# IMU.net
KiCad netlist of a schematic drawn in Altium Designer
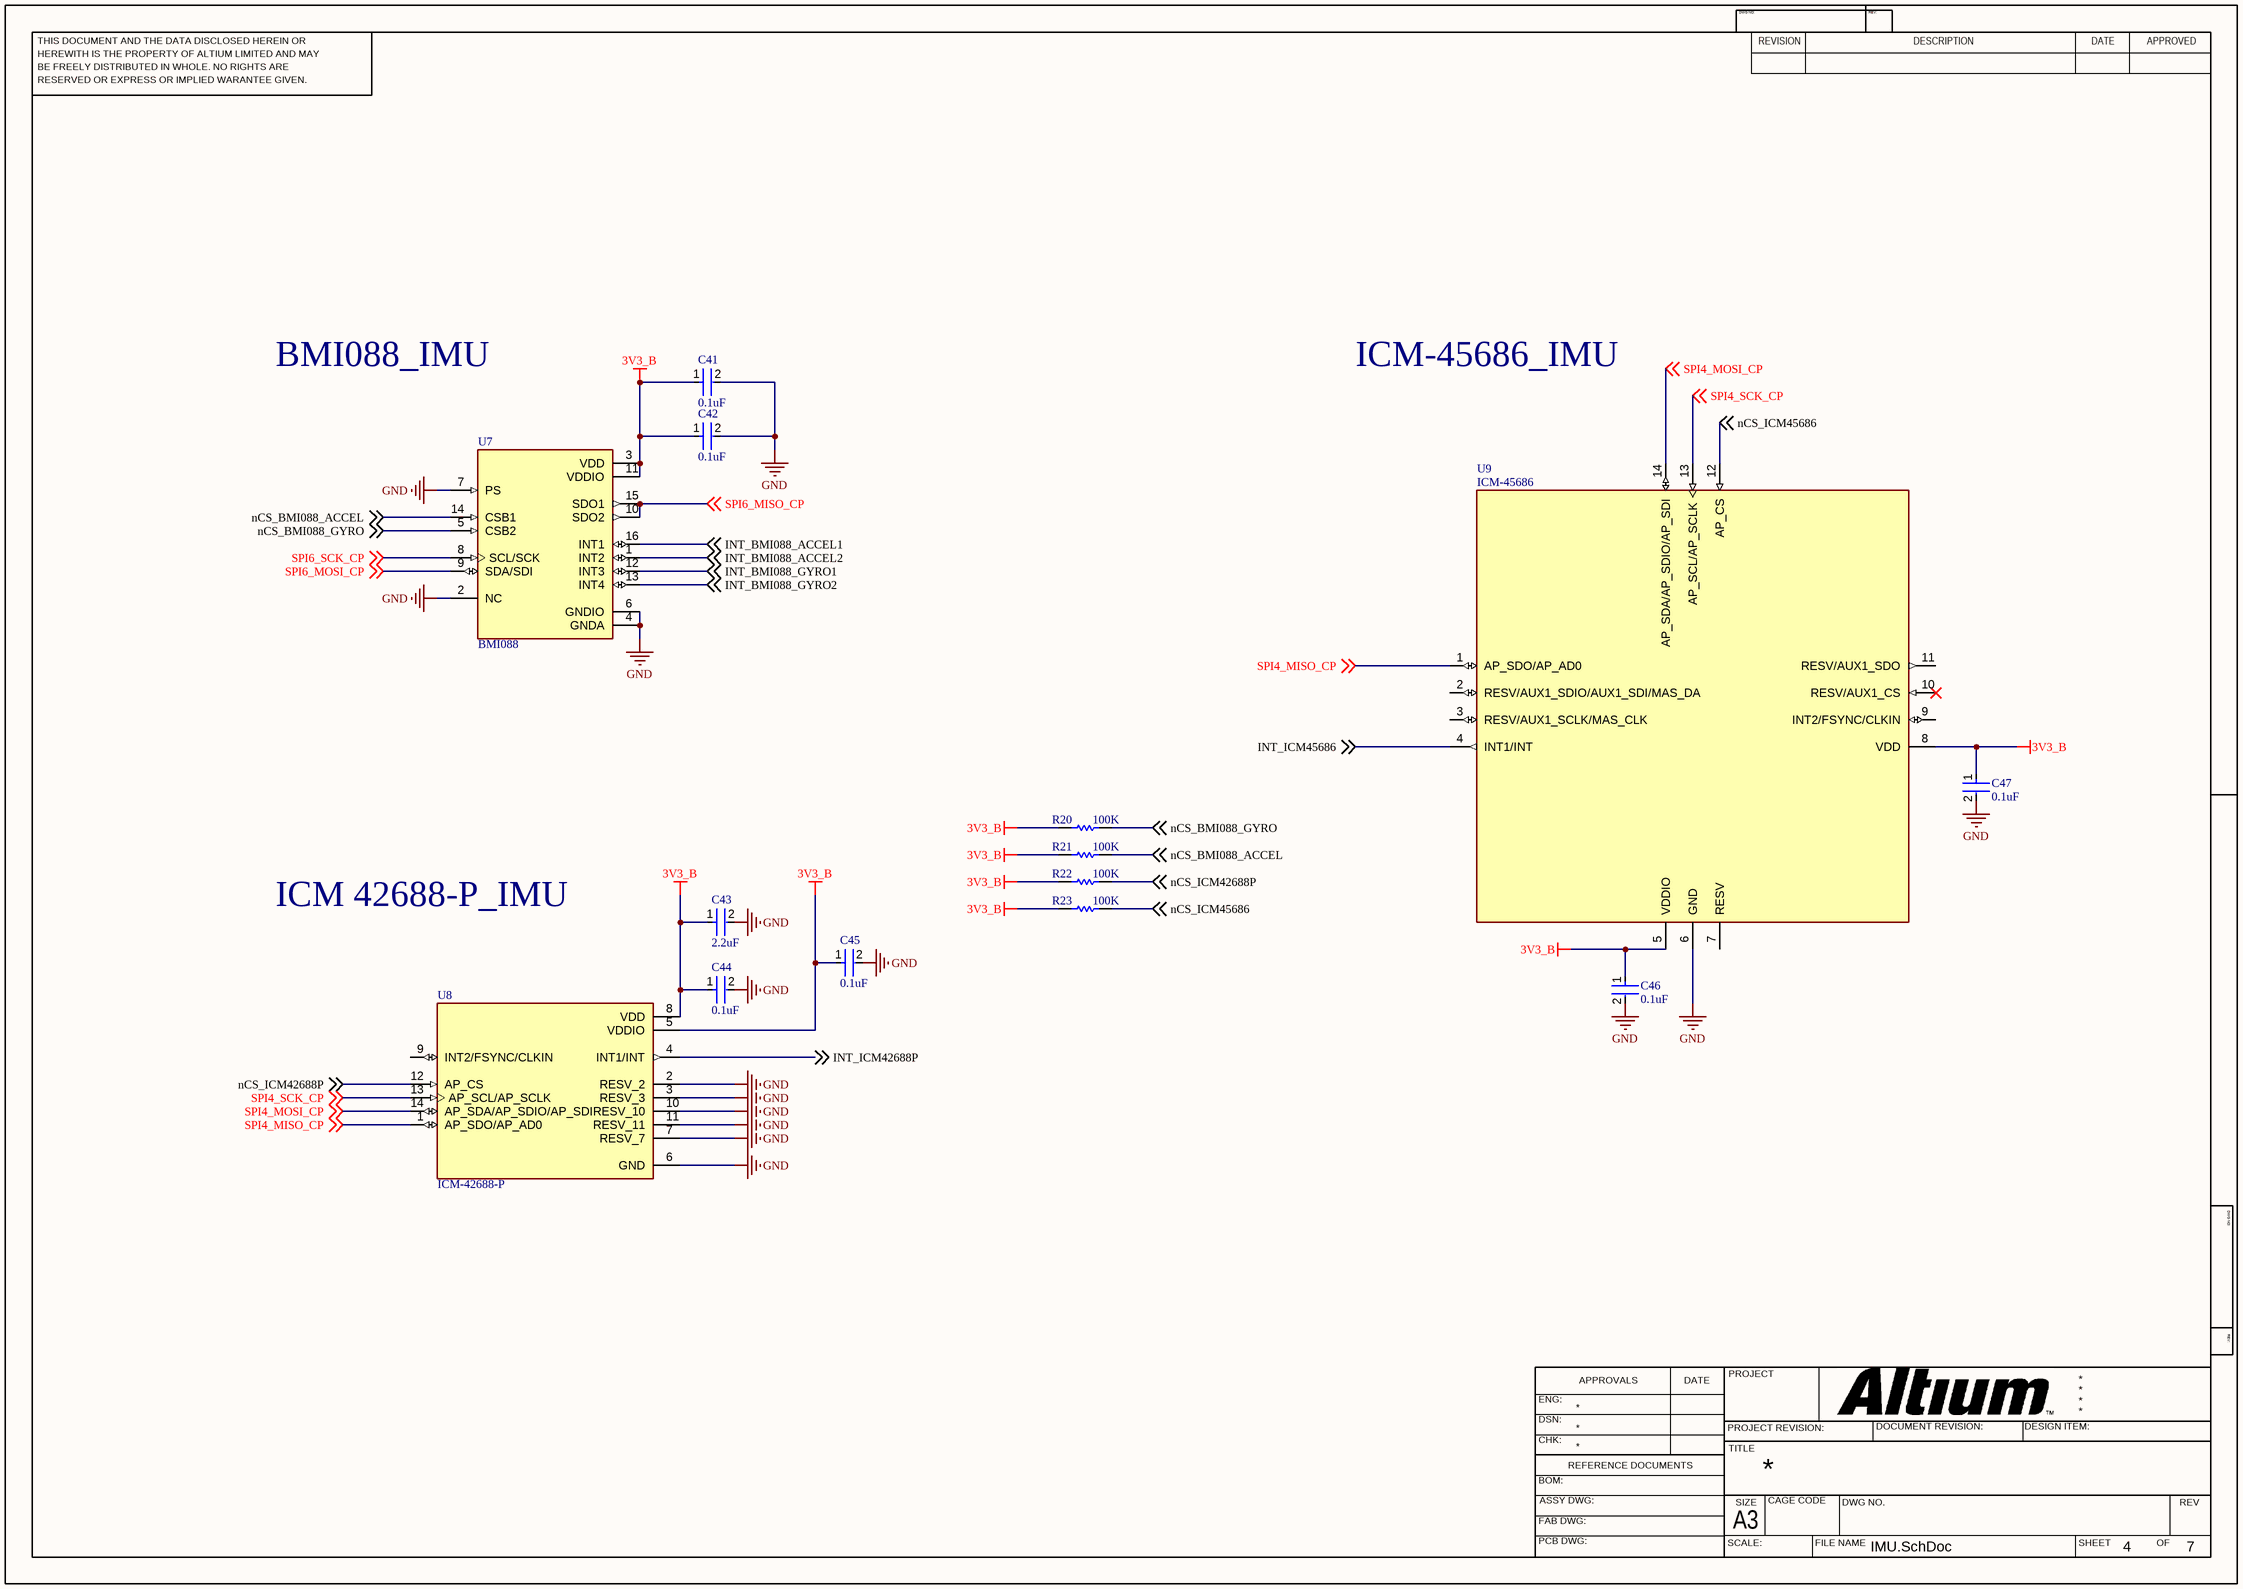
[diagram p0: IMU.SchDoc]

(export (version "E")
  (design (tool "Eeschema 10.0.6"))
  (components
    (comp (ref "C41")
      (value "0.1uF")
      (footprint "FP-C0603C-CF-MFG")
      (description "CAP CER 0.1UF 50V X7R 0603")
      (fields (field (name "TOLERANCE") "0.1") (field (name "MANUFACTURER") "KEMET"))
      (libsource (lib "Altium Content Vault") (part "b4654b650e69147ec39a6b967a45e02"))
    )
    (comp (ref "C42")
      (value "0.1uF")
      (footprint "FP-C0603C-CF-MFG")
      (description "CAP CER 0.1UF 50V X7R 0603")
      (fields (field (name "TOLERANCE") "0.1") (field (name "MANUFACTURER") "KEMET"))
      (libsource (lib "Altium Content Vault") (part "b4654b650e69147ec39a6b967a45e02"))
    )
    (comp (ref "C43")
      (value "2.2uF")
      (footprint "FP-GRM188-0_1-e0_2_0_5-MFG")
      (description "Chip Multilayer Ceramic Capacitors for General Purpose, 0603, 2.2uF, X7R, 15%, 10%, 10V")
      (fields (field (name "VOLTAGE") "10V") (field (name "TOLERANCE") "10%"))
      (libsource (lib "Altium Content Vault") (part "11868f565c42a9108669ba33697ecf6"))
    )
    (comp (ref "C44")
      (value "0.1uF")
      (footprint "FP-C0603C-CF-MFG")
      (description "CAP CER 0.1UF 50V X7R 0603")
      (fields (field (name "TOLERANCE") "0.1") (field (name "MANUFACTURER") "KEMET"))
      (libsource (lib "Altium Content Vault") (part "b4654b650e69147ec39a6b967a45e02"))
    )
    (comp (ref "C45")
      (value "0.1uF")
      (footprint "FP-C0603C-CF-MFG")
      (description "CAP CER 0.1UF 50V X7R 0603")
      (fields (field (name "TOLERANCE") "0.1") (field (name "MANUFACTURER") "KEMET"))
      (libsource (lib "Altium Content Vault") (part "b4654b650e69147ec39a6b967a45e02"))
    )
    (comp (ref "C46")
      (value "0.1uF")
      (footprint "FP-C0603C-CF-MFG")
      (description "CAP CER 0.1UF 50V X7R 0603")
      (fields (field (name "TOLERANCE") "0.1") (field (name "MANUFACTURER") "KEMET"))
      (libsource (lib "Altium Content Vault") (part "b4654b650e69147ec39a6b967a45e02"))
    )
    (comp (ref "C47")
      (value "0.1uF")
      (footprint "FP-C0603C-CF-MFG")
      (description "CAP CER 0.1UF 50V X7R 0603")
      (fields (field (name "TOLERANCE") "0.1") (field (name "MANUFACTURER") "KEMET"))
      (libsource (lib "Altium Content Vault") (part "b4654b650e69147ec39a6b967a45e02"))
    )
    (comp (ref "R20")
      (value "100K")
      (footprint "RESC1608X55X30ML20T10")
      (fields (field (name "PART NUMBER") "RK73B1JTTD104J") (field (name "MANUFACTURER") "KOA Speer"))
      (libsource (lib "Altium Content Vault") (part "RES"))
    )
    (comp (ref "R21")
      (value "100K")
      (footprint "RESC1608X55X30ML20T10")
      (fields (field (name "PART NUMBER") "RK73B1JTTD104J") (field (name "MANUFACTURER") "KOA Speer"))
      (libsource (lib "Altium Content Vault") (part "RES"))
    )
    (comp (ref "R22")
      (value "100K")
      (footprint "RESC1608X55X30ML20T10")
      (fields (field (name "PART NUMBER") "RK73B1JTTD104J") (field (name "MANUFACTURER") "KOA Speer"))
      (libsource (lib "Altium Content Vault") (part "RES"))
    )
    (comp (ref "R23")
      (value "100K")
      (footprint "RESC1608X55X30ML20T10")
      (fields (field (name "PART NUMBER") "RK73B1JTTD104J") (field (name "MANUFACTURER") "KOA Speer"))
      (libsource (lib "Altium Content Vault") (part "RES"))
    )
    (comp (ref "U7")
      (value "BMI088")
      (footprint "PQFN50P450X300X100-16N")
      (libsource (lib "Hitesh Bhoyar") (part "BMI088"))
    )
    (comp (ref "U8")
      (value "ICM-42688-P")
      (footprint "PQFN50P300X250X97-14N")
      (description "Accelerometer, Gyroscope, 6 Axis Sensor Output")
      (libsource (lib "Hitesh Bhoyar") (part "ICM-42688-P"))
    )
    (comp (ref "U9")
      (value "ICM-45686")
      (footprint "IC_ICM-45686")
      (description "Accelerometer, Gyroscope, 6 Axis Sensor I2C, I3C, SPI Output")
      (fields (field (name "MF") "TDK InvenSense"))
      (libsource (lib "Hitesh Bhoyar") (part "ICM-45686"))
    )
  )
  (nets
    (net (code "1") (name "3V3_B") (class "Default")
      (node (ref "C41") (pin "1") (pinfunction "1_1") (pintype "passive"))
      (node (ref "C42") (pin "1") (pinfunction "1_1") (pintype "passive"))
      (node (ref "C43") (pin "1") (pinfunction "1_1") (pintype "passive"))
      (node (ref "C44") (pin "1") (pinfunction "1_1") (pintype "passive"))
      (node (ref "C45") (pin "1") (pinfunction "1_1") (pintype "passive"))
      (node (ref "C46") (pin "1") (pinfunction "1_1") (pintype "passive"))
      (node (ref "C47") (pin "1") (pinfunction "1_1") (pintype "passive"))
      (node (ref "R20") (pin "2") (pinfunction "2_2") (pintype "passive"))
      (node (ref "R21") (pin "2") (pinfunction "2_2") (pintype "passive"))
      (node (ref "R22") (pin "2") (pinfunction "2_2") (pintype "passive"))
      (node (ref "R23") (pin "2") (pinfunction "2_2") (pintype "passive"))
      (node (ref "U7") (pin "11") (pinfunction "VDDIO_11") (pintype "power_in"))
      (node (ref "U7") (pin "3") (pinfunction "VDD_3") (pintype "power_in"))
      (node (ref "U8") (pin "5") (pinfunction "VDDIO_5") (pintype "power_in"))
      (node (ref "U8") (pin "8") (pinfunction "VDD_8") (pintype "power_in"))
      (node (ref "U9") (pin "5") (pinfunction "VDDIO_5") (pintype "power_in"))
      (node (ref "U9") (pin "8") (pinfunction "VDD_8") (pintype "power_in"))
    )
    (net (code "2") (name "GND") (class "Default")
      (node (ref "C41") (pin "2") (pinfunction "2_2") (pintype "passive"))
      (node (ref "C42") (pin "2") (pinfunction "2_2") (pintype "passive"))
      (node (ref "C43") (pin "2") (pinfunction "2_2") (pintype "passive"))
      (node (ref "C44") (pin "2") (pinfunction "2_2") (pintype "passive"))
      (node (ref "C45") (pin "2") (pinfunction "2_2") (pintype "passive"))
      (node (ref "C46") (pin "2") (pinfunction "2_2") (pintype "passive"))
      (node (ref "C47") (pin "2") (pinfunction "2_2") (pintype "passive"))
      (node (ref "U7") (pin "2") (pinfunction "NC_2") (pintype "passive"))
      (node (ref "U7") (pin "4") (pinfunction "GNDA_4") (pintype "power_in"))
      (node (ref "U7") (pin "6") (pinfunction "GNDIO_6") (pintype "power_in"))
      (node (ref "U7") (pin "7") (pinfunction "PS_7") (pintype "input"))
      (node (ref "U8") (pin "10") (pinfunction "RESV_10_10") (pintype "passive"))
      (node (ref "U8") (pin "11") (pinfunction "RESV_11_11") (pintype "passive"))
      (node (ref "U8") (pin "2") (pinfunction "RESV_2_2") (pintype "passive"))
      (node (ref "U8") (pin "3") (pinfunction "RESV_3_3") (pintype "passive"))
      (node (ref "U8") (pin "6") (pinfunction "GND_6") (pintype "power_in"))
      (node (ref "U8") (pin "7") (pinfunction "RESV_7_7") (pintype "passive"))
      (node (ref "U9") (pin "6") (pinfunction "GND_6") (pintype "power_in"))
    )
    (net (code "3") (name "INT_BMI088_ACCEL1") (class "Default")
      (node (ref "U7") (pin "16") (pinfunction "INT1_16") (pintype "bidirectional"))
    )
    (net (code "4") (name "INT_BMI088_ACCEL2") (class "Default")
      (node (ref "U7") (pin "1") (pinfunction "INT2_1") (pintype "bidirectional"))
    )
    (net (code "5") (name "INT_BMI088_GYRO1") (class "Default")
      (node (ref "U7") (pin "12") (pinfunction "INT3_12") (pintype "bidirectional"))
    )
    (net (code "6") (name "INT_BMI088_GYRO2") (class "Default")
      (node (ref "U7") (pin "13") (pinfunction "INT4_13") (pintype "bidirectional"))
    )
    (net (code "7") (name "INT_ICM42688P") (class "Default")
      (node (ref "U8") (pin "4") (pinfunction "INT1/INT_4") (pintype "output"))
    )
    (net (code "8") (name "INT_ICM45686") (class "Default")
      (node (ref "U9") (pin "4") (pinfunction "INT1/INT_4") (pintype "output"))
    )
    (net (code "9") (name "SPI4_MISO_CP") (class "Default")
      (node (ref "U8") (pin "1") (pinfunction "AP_SDO/AP_AD0_1") (pintype "bidirectional"))
      (node (ref "U9") (pin "1") (pinfunction "AP_SDO/AP_AD0_1") (pintype "bidirectional"))
    )
    (net (code "10") (name "SPI4_MOSI_CP") (class "Default")
      (node (ref "U8") (pin "14") (pinfunction "AP_SDA/AP_SDIO/AP_SDI_14") (pintype "bidirectional"))
      (node (ref "U9") (pin "14") (pinfunction "AP_SDA/AP_SDIO/AP_SDI_14") (pintype "bidirectional"))
    )
    (net (code "11") (name "SPI4_SCK_CP") (class "Default")
      (node (ref "U8") (pin "13") (pinfunction "AP_SCL/AP_SCLK_13") (pintype "input"))
      (node (ref "U9") (pin "13") (pinfunction "AP_SCL/AP_SCLK_13") (pintype "input"))
    )
    (net (code "12") (name "SPI6_MISO_CP") (class "Default")
      (node (ref "U7") (pin "10") (pinfunction "SDO2_10") (pintype "output"))
      (node (ref "U7") (pin "15") (pinfunction "SDO1_15") (pintype "output"))
    )
    (net (code "13") (name "SPI6_MOSI_CP") (class "Default")
      (node (ref "U7") (pin "9") (pinfunction "SDA/SDI_9") (pintype "bidirectional"))
    )
    (net (code "14") (name "SPI6_SCK_CP") (class "Default")
      (node (ref "U7") (pin "8") (pinfunction "SCL/SCK_8") (pintype "input"))
    )
    (net (code "15") (name "nCS_BMI088_ACCEL") (class "Default")
      (node (ref "R21") (pin "1") (pinfunction "1_1") (pintype "passive"))
      (node (ref "U7") (pin "14") (pinfunction "CSB1_14") (pintype "input"))
    )
    (net (code "16") (name "nCS_BMI088_GYRO") (class "Default")
      (node (ref "R20") (pin "1") (pinfunction "1_1") (pintype "passive"))
      (node (ref "U7") (pin "5") (pinfunction "CSB2_5") (pintype "input"))
    )
    (net (code "17") (name "nCS_ICM42688P") (class "Default")
      (node (ref "R22") (pin "1") (pinfunction "1_1") (pintype "passive"))
      (node (ref "U8") (pin "12") (pinfunction "AP_CS_12") (pintype "input"))
    )
    (net (code "18") (name "nCS_ICM45686") (class "Default")
      (node (ref "R23") (pin "1") (pinfunction "1_1") (pintype "passive"))
      (node (ref "U9") (pin "12") (pinfunction "AP_CS_12") (pintype "input"))
    )
    (net (code "19") (name "unconnected-(U8-INT2{slash}FSYNC{slash}CLKIN-Pad9)") (class "Default")
      (node (ref "U8") (pin "9") (pinfunction "INT2/FSYNC/CLKIN_9") (pintype "bidirectional"))
    )
    (net (code "20") (name "unconnected-(U9-INT2{slash}FSYNC{slash}CLKIN-Pad9)") (class "Default")
      (node (ref "U9") (pin "9") (pinfunction "INT2/FSYNC/CLKIN_9") (pintype "bidirectional"))
    )
    (net (code "21") (name "unconnected-(U9-RESV-Pad7)") (class "Default")
      (node (ref "U9") (pin "7") (pinfunction "RESV_7") (pintype "passive"))
    )
    (net (code "22") (name "unconnected-(U9-RESV{slash}AUX1_CS-Pad10)") (class "Default")
      (node (ref "U9") (pin "10") (pinfunction "RESV/AUX1_CS_10") (pintype "input+no_connect"))
    )
    (net (code "23") (name "unconnected-(U9-RESV{slash}AUX1_SCLK{slash}MAS_CLK-Pad3)") (class "Default")
      (node (ref "U9") (pin "3") (pinfunction "RESV/AUX1_SCLK/MAS_CLK_3") (pintype "bidirectional"))
    )
    (net (code "24") (name "unconnected-(U9-RESV{slash}AUX1_SDIO{slash}AUX1_SDI{slash}MAS_DA-Pad2)") (class "Default")
      (node (ref "U9") (pin "2") (pinfunction "RESV/AUX1_SDIO/AUX1_SDI/MAS_DA_2") (pintype "bidirectional"))
    )
    (net (code "25") (name "unconnected-(U9-RESV{slash}AUX1_SDO-Pad11)") (class "Default")
      (node (ref "U9") (pin "11") (pinfunction "RESV/AUX1_SDO_11") (pintype "output"))
    )
  )
)
